# FWBC_v1.net
KiCad netlist of a schematic drawn in EAGLE
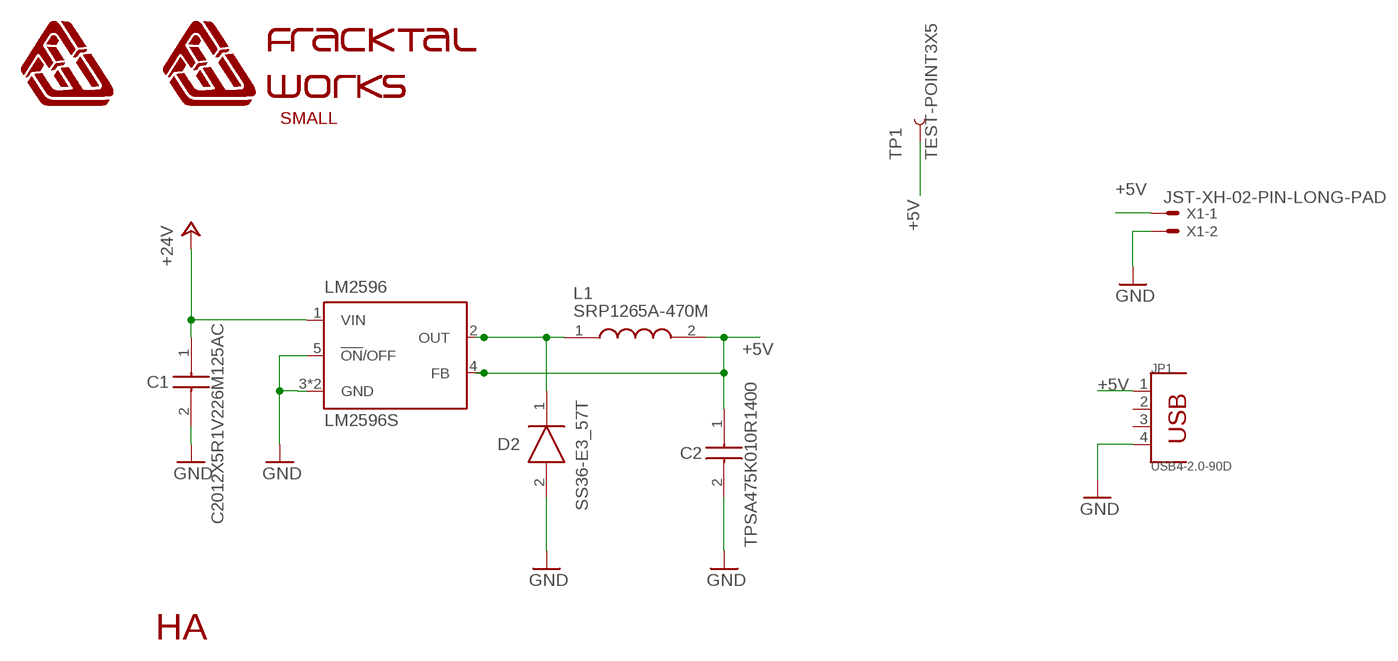
[diagram p0: schematic, sheet 1]

(export (version "E")
  (design (tool "Eeschema 10.0.6"))
  (components
    (comp (ref "C1")
      (value "C2012X5R1V226M125AC")
      (footprint "eagle-import:CAPC2012X145N")
      (fields
        (field (name "MOUSER_PART_NUMBER") "810-C2012X5R1V226MAC")
        (field (name "RS_PART_NUMBER") "9159334P")
      )
      (libsource (lib "eagle-import") (part "C2012X5R1V226M125AC"))
    )
    (comp (ref "C2")
      (value "TPSA475K010R1400")
      (footprint "eagle-import:CAPPM3216X180N")
      (fields
        (field (name "MOUSER_PART_NUMBER") "581-TPSA475K010R1400")
        (field (name "RS_PART_NUMBER") "1366129")
      )
      (libsource (lib "eagle-import") (part "TPSA475K010R1400"))
    )
    (comp (ref "D2")
      (value "SS36-E3_57T")
      (footprint "eagle-import:DIOM7959X262N")
      (fields
        (field (name "MANUFACTURER_PART_NUMBER") "SS36-E3/57T")
        (field (name "MOUSER_PART_NUMBER") "625-SS36-E3")
        (field (name "RS_PART_NUMBER") "7000975P")
      )
      (libsource (lib "eagle-import") (part "SS36-E3_57T"))
    )
    (comp (ref "JP1")
      (value "USB4-2.0-90D")
      (footprint "eagle-import:USB4+2P-2.0-90D")
      (libsource (lib "eagle-import") (part "DIP-USB-A-TYPE-FMAL(4+2P-2.0-90D)"))
    )
    (comp (ref "L1")
      (value "SRP1265A-470M")
      (footprint "eagle-import:SRP1265A")
      (fields
        (field (name "MOUSER_PART_NUMBER") "652-SRP1265A-470M")
        (field (name "RS_PART_NUMBER") "8193513P")
      )
      (libsource (lib "eagle-import") (part "SRP1265A-470M"))
    )
    (comp (ref "LM2596")
      (value "LM2596S")
      (footprint "eagle-import:LM2596_TO263-5")
      (fields (field (name "MF") "NATIONAL SEMICONDUCTOR") (field (name "MPN") "LM2596S-ADJ/NOPB"))
      (libsource (lib "eagle-import") (part "LM2596S"))
    )
    (comp (ref "M_HA_1")
      (value "HA_MARK")
      (footprint "eagle-import:HA_MARK")
      (libsource (lib "eagle-import") (part "HA_MARK"))
    )
    (comp (ref "TP1")
      (value "TEST-POINT3X5")
      (footprint "eagle-import:PAD.03X.05")
      (libsource (lib "eagle-import") (part "TEST-POINT3X5"))
    )
    (comp (ref "U$1")
      (value "FWLOGO")
      (footprint "eagle-import:FWLOGO")
      (libsource (lib "eagle-import") (part "FWLOGO"))
    )
    (comp (ref "U$2")
      (value "FWLOGO_TEXT_SMALL")
      (footprint "eagle-import:FWLOGO_TEXT_SMALL")
      (libsource (lib "eagle-import") (part "FWLOGO_TEXT_SMALL"))
    )
    (comp (ref "X1")
      (value "JST-XH-02-PIN-LONG-PAD")
      (footprint "eagle-import:JST-XH-02-PACKAGE-LONG-PAD")
      (libsource (lib "eagle-import") (part "JST-XH-02-PIN-LONG-PAD"))
    )
  )
  (nets
    (net (code "1") (name "+24V") (class "Default")
      (node (ref "C1") (pin "1") (pinfunction "1_1") (pintype "bidirectional"))
      (node (ref "LM2596") (pin "1") (pinfunction "VIN_1") (pintype "input"))
    )
    (net (code "2") (name "/+5V") (class "Default")
      (node (ref "C2") (pin "1") (pinfunction "1_1") (pintype "bidirectional"))
      (node (ref "JP1") (pin "1") (pinfunction "1_1") (pintype "bidirectional"))
      (node (ref "L1") (pin "2") (pinfunction "2_2") (pintype "bidirectional"))
      (node (ref "LM2596") (pin "4") (pinfunction "FB_4") (pintype "input"))
      (node (ref "TP1") (pin "P$1") (pinfunction "1_P$1") (pintype "bidirectional"))
      (node (ref "X1") (pin "1") (pinfunction "S_1") (pintype "passive"))
    )
    (net (code "3") (name "GND") (class "Default")
      (node (ref "C1") (pin "2") (pinfunction "2_2") (pintype "bidirectional"))
      (node (ref "C2") (pin "2") (pinfunction "2_2") (pintype "bidirectional"))
      (node (ref "D2") (pin "2") (pinfunction "A_2") (pintype "bidirectional"))
      (node (ref "JP1") (pin "4") (pinfunction "4_4") (pintype "bidirectional"))
      (node (ref "LM2596") (pin "3") (pinfunction "GND_3") (pintype "power_in"))
      (node (ref "LM2596") (pin "5") (pinfunction "~{ON}/OFF_5") (pintype "input"))
      (node (ref "LM2596") (pin "6") (pinfunction "GND_6") (pintype "power_in"))
      (node (ref "X1") (pin "2") (pinfunction "S_2") (pintype "passive"))
    )
    (net (code "4") (name "Net-(D2-K)") (class "Default")
      (node (ref "D2") (pin "1") (pinfunction "K_1") (pintype "bidirectional"))
      (node (ref "L1") (pin "1") (pinfunction "1_1") (pintype "bidirectional"))
      (node (ref "LM2596") (pin "2") (pinfunction "OUT_2") (pintype "output"))
    )
    (net (code "5") (name "unconnected-(JP1-Pad2)") (class "Default")
      (node (ref "JP1") (pin "2") (pinfunction "2_2") (pintype "bidirectional"))
    )
    (net (code "6") (name "unconnected-(JP1-Pad3)") (class "Default")
      (node (ref "JP1") (pin "3") (pinfunction "3_3") (pintype "bidirectional"))
    )
  )
)
